# nano_relay.net
KiCad netlist of a schematic drawn in EAGLE
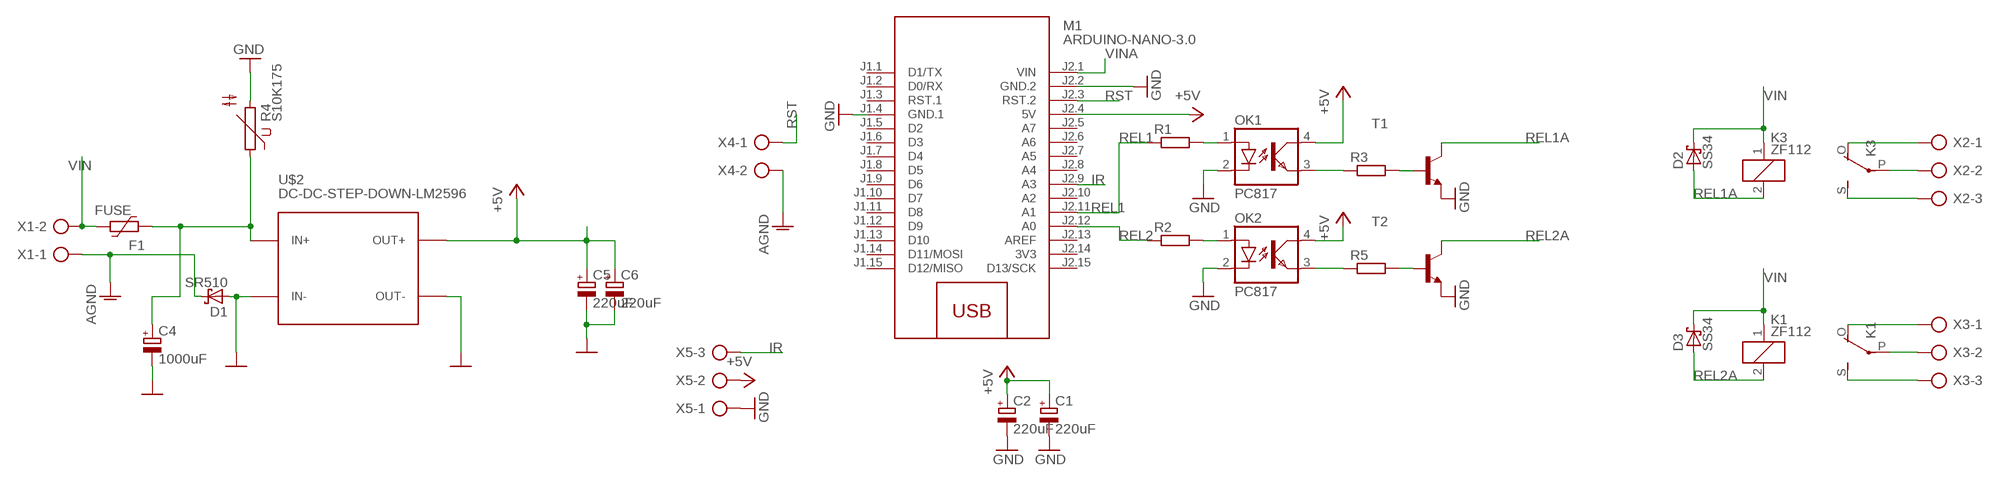
[diagram p0: schematic, sheet 1]

(export (version "E")
  (design (tool "Eeschema 10.0.6"))
  (components
    (comp (ref "C1")
      (value "220uF")
      (footprint "eagle-import:E2,5-7")
      (libsource (lib "eagle-import") (part "CPOL-EUE2.5-7"))
    )
    (comp (ref "C2")
      (value "220uF")
      (footprint "eagle-import:E2,5-7")
      (libsource (lib "eagle-import") (part "CPOL-EUE2.5-7"))
    )
    (comp (ref "C4")
      (value "1000uF")
      (footprint "eagle-import:E5-8,5")
      (libsource (lib "eagle-import") (part "CPOL-EUE5-8.5"))
    )
    (comp (ref "C5")
      (value "220uF")
      (footprint "eagle-import:E2,5-7")
      (libsource (lib "eagle-import") (part "CPOL-EUE2.5-7"))
    )
    (comp (ref "C6")
      (value "220uF")
      (footprint "eagle-import:E2,5-7")
      (libsource (lib "eagle-import") (part "CPOL-EUE2.5-7"))
    )
    (comp (ref "D1")
      (value "SR510")
      (footprint "eagle-import:SMB")
      (libsource (lib "eagle-import") (part "SCHOTTKY-DIODESMD"))
    )
    (comp (ref "D2")
      (value "SS34")
      (footprint "eagle-import:SMB")
      (libsource (lib "eagle-import") (part "SCHOTTKY-DIODESMD"))
    )
    (comp (ref "D3")
      (value "SS34")
      (footprint "eagle-import:SMB")
      (libsource (lib "eagle-import") (part "SCHOTTKY-DIODESMD"))
    )
    (comp (ref "F1")
      (value "FUSE")
      (footprint "eagle-import:1812L")
      (fields (field (name "MF") "Littelfuse") (field (name "MPN") "1812L010"))
      (libsource (lib "eagle-import") (part "?1812L010"))
    )
    (comp (ref "K1")
      (value "ZF112")
      (footprint "eagle-import:ZF112")
      (libsource (lib "eagle-import") (part "ZF112"))
    )
    (comp (ref "K3")
      (value "ZF112")
      (footprint "eagle-import:ZF112")
      (libsource (lib "eagle-import") (part "ZF112"))
    )
    (comp (ref "M1")
      (value "ARDUINO-NANO-3.0")
      (footprint "eagle-import:ARDUINO-NANO-3.0")
      (libsource (lib "eagle-import") (part "ARDUINO-NANO-3.0"))
    )
    (comp (ref "OK1")
      (value "PC817")
      (footprint "eagle-import:DIL04")
      (fields (field (name "MPN") "PC817X4J000F"))
      (libsource (lib "eagle-import") (part "PC817"))
    )
    (comp (ref "OK2")
      (value "PC817")
      (footprint "eagle-import:DIL04")
      (fields (field (name "MPN") "PC817X4J000F"))
      (libsource (lib "eagle-import") (part "PC817"))
    )
    (comp (ref "R1")
      (value "R-EU_M0805")
      (footprint "eagle-import:M0805")
      (libsource (lib "eagle-import") (part "R-EU_M0805"))
    )
    (comp (ref "R2")
      (value "R-EU_M0805")
      (footprint "eagle-import:M0805")
      (libsource (lib "eagle-import") (part "R-EU_M0805"))
    )
    (comp (ref "R3")
      (value "R-EU_M0805")
      (footprint "eagle-import:M0805")
      (libsource (lib "eagle-import") (part "R-EU_M0805"))
    )
    (comp (ref "R4")
      (value "S10K175")
      (footprint "eagle-import:S10K175")
      (libsource (lib "eagle-import") (part "S10K175"))
    )
    (comp (ref "R5")
      (value "R-EU_M0805")
      (footprint "eagle-import:M0805")
      (libsource (lib "eagle-import") (part "R-EU_M0805"))
    )
    (comp (ref "T1")
      (value "MMBT2222ALT1-NPN-SOT23-BEC")
      (footprint "eagle-import:SOT23-BEC")
      (libsource (lib "eagle-import") (part "-NPN-SOT23-BECMMBT2222ALT1"))
    )
    (comp (ref "T2")
      (value "MMBT2222ALT1-NPN-SOT23-BEC")
      (footprint "eagle-import:SOT23-BEC")
      (libsource (lib "eagle-import") (part "-NPN-SOT23-BECMMBT2222ALT1"))
    )
    (comp (ref "U$2")
      (value "DC-DC-STEP-DOWN-LM2596")
      (footprint "eagle-import:DC-DC-STEP-DOWN-LM2596")
      (libsource (lib "eagle-import") (part "DC-DC-STEP-DOWN-LM2596"))
    )
    (comp (ref "X1")
      (value "AK300/2")
      (footprint "eagle-import:AK300_2")
      (libsource (lib "eagle-import") (part "AK300/2"))
    )
    (comp (ref "X2")
      (value "AK300/3")
      (footprint "eagle-import:AK300_3")
      (libsource (lib "eagle-import") (part "AK300/3"))
    )
    (comp (ref "X3")
      (value "AK300/3")
      (footprint "eagle-import:AK300_3")
      (libsource (lib "eagle-import") (part "AK300/3"))
    )
    (comp (ref "X4")
      (value "AK300/2")
      (footprint "eagle-import:AK300_2")
      (libsource (lib "eagle-import") (part "AK300/2"))
    )
    (comp (ref "X5")
      (value "AK300/3")
      (footprint "eagle-import:AK300_3")
      (libsource (lib "eagle-import") (part "AK300/3"))
    )
  )
  (nets
    (net (code "1") (name "+5V") (class "Default")
      (node (ref "C1") (pin "+") (pinfunction "+_+") (pintype "passive"))
      (node (ref "C2") (pin "+") (pinfunction "+_+") (pintype "passive"))
      (node (ref "C5") (pin "+") (pinfunction "+_+") (pintype "passive"))
      (node (ref "C6") (pin "+") (pinfunction "+_+") (pintype "passive"))
      (node (ref "M1") (pin "J2.4") (pinfunction "5V_J2.4") (pintype "power_in"))
      (node (ref "OK1") (pin "4") (pinfunction "COL_4") (pintype "passive"))
      (node (ref "OK2") (pin "4") (pinfunction "COL_4") (pintype "passive"))
      (node (ref "U$2") (pin "OUT+") (pinfunction "OUT+_OUT+") (pintype "bidirectional"))
      (node (ref "X5") (pin "2") (pinfunction "KL_2") (pintype "passive"))
    )
    (net (code "2") (name "/3V3") (class "Default")
      (node (ref "M1") (pin "J2.14") (pinfunction "3V3_J2.14") (pintype "power_in"))
    )
    (net (code "3") (name "/IR") (class "Default")
      (node (ref "M1") (pin "J2.9") (pinfunction "A3_J2.9") (pintype "bidirectional"))
      (node (ref "X5") (pin "3") (pinfunction "KL_3") (pintype "passive"))
    )
    (net (code "4") (name "/REL1") (class "Default")
      (node (ref "M1") (pin "J2.11") (pinfunction "A1_J2.11") (pintype "bidirectional"))
      (node (ref "R1") (pin "1") (pinfunction "1_1") (pintype "passive"))
    )
    (net (code "5") (name "/REL1A") (class "Default")
      (node (ref "D2") (pin "A") (pinfunction "A_A") (pintype "passive"))
      (node (ref "K3") (pin "2") (pinfunction "2_2") (pintype "passive"))
      (node (ref "T1") (pin "C") (pinfunction "C_C") (pintype "passive"))
    )
    (net (code "6") (name "/REL2") (class "Default")
      (node (ref "M1") (pin "J2.12") (pinfunction "A0_J2.12") (pintype "bidirectional"))
      (node (ref "R2") (pin "1") (pinfunction "1_1") (pintype "passive"))
    )
    (net (code "7") (name "/REL2A") (class "Default")
      (node (ref "D3") (pin "A") (pinfunction "A_A") (pintype "passive"))
      (node (ref "K1") (pin "2") (pinfunction "2_2") (pintype "passive"))
      (node (ref "T2") (pin "C") (pinfunction "C_C") (pintype "passive"))
    )
    (net (code "8") (name "/RST") (class "Default")
      (node (ref "M1") (pin "J2.3") (pinfunction "RST.2_J2.3") (pintype "bidirectional"))
      (node (ref "X4") (pin "1") (pinfunction "KL_1") (pintype "passive"))
    )
    (net (code "9") (name "/VIN") (class "Default")
      (node (ref "D2") (pin "C") (pinfunction "C_C") (pintype "passive"))
      (node (ref "D3") (pin "C") (pinfunction "C_C") (pintype "passive"))
      (node (ref "F1") (pin "1") (pinfunction "1_1") (pintype "passive"))
      (node (ref "K1") (pin "1") (pinfunction "1_1") (pintype "passive"))
      (node (ref "K3") (pin "1") (pinfunction "1_1") (pintype "passive"))
      (node (ref "X1") (pin "2") (pinfunction "KL_2") (pintype "passive"))
    )
    (net (code "10") (name "/VINA") (class "Default")
      (node (ref "M1") (pin "J2.1") (pinfunction "VIN_J2.1") (pintype "power_in"))
    )
    (net (code "11") (name "AGND") (class "Default")
      (node (ref "D1") (pin "C") (pinfunction "C_C") (pintype "passive"))
      (node (ref "X1") (pin "1") (pinfunction "KL_1") (pintype "passive"))
      (node (ref "X4") (pin "2") (pinfunction "KL_2") (pintype "passive"))
    )
    (net (code "12") (name "GND") (class "Default")
      (node (ref "C1") (pin "-") (pinfunction "-_-") (pintype "passive"))
      (node (ref "C2") (pin "-") (pinfunction "-_-") (pintype "passive"))
      (node (ref "C4") (pin "-") (pinfunction "-_-") (pintype "passive"))
      (node (ref "C5") (pin "-") (pinfunction "-_-") (pintype "passive"))
      (node (ref "C6") (pin "-") (pinfunction "-_-") (pintype "passive"))
      (node (ref "D1") (pin "A") (pinfunction "A_A") (pintype "passive"))
      (node (ref "M1") (pin "J1.4") (pinfunction "GND.1_J1.4") (pintype "power_in"))
      (node (ref "M1") (pin "J2.2") (pinfunction "GND.2_J2.2") (pintype "power_in"))
      (node (ref "OK1") (pin "2") (pinfunction "C_2") (pintype "passive"))
      (node (ref "OK2") (pin "2") (pinfunction "C_2") (pintype "passive"))
      (node (ref "R4") (pin "2") (pinfunction "2_2") (pintype "passive"))
      (node (ref "T1") (pin "E") (pinfunction "E_E") (pintype "passive"))
      (node (ref "T2") (pin "E") (pinfunction "E_E") (pintype "passive"))
      (node (ref "U$2") (pin "IN-") (pinfunction "IN-_IN-") (pintype "bidirectional"))
      (node (ref "U$2") (pin "OUT-") (pinfunction "OUT-_OUT-") (pintype "bidirectional"))
      (node (ref "X5") (pin "1") (pinfunction "KL_1") (pintype "passive"))
    )
    (net (code "13") (name "Net-(C4-Pad+)") (class "Default")
      (node (ref "C4") (pin "+") (pinfunction "+_+") (pintype "passive"))
      (node (ref "F1") (pin "2") (pinfunction "2_2") (pintype "passive"))
      (node (ref "R4") (pin "1") (pinfunction "1_1") (pintype "passive"))
      (node (ref "U$2") (pin "IN+") (pinfunction "IN+_IN+") (pintype "bidirectional"))
    )
    (net (code "14") (name "Net-(OK1-A)") (class "Default")
      (node (ref "OK1") (pin "1") (pinfunction "A_1") (pintype "passive"))
      (node (ref "R1") (pin "2") (pinfunction "2_2") (pintype "passive"))
    )
    (net (code "15") (name "Net-(OK1-EMIT)") (class "Default")
      (node (ref "OK1") (pin "3") (pinfunction "EMIT_3") (pintype "passive"))
      (node (ref "R3") (pin "1") (pinfunction "1_1") (pintype "passive"))
    )
    (net (code "16") (name "Net-(OK2-A)") (class "Default")
      (node (ref "OK2") (pin "1") (pinfunction "A_1") (pintype "passive"))
      (node (ref "R2") (pin "2") (pinfunction "2_2") (pintype "passive"))
    )
    (net (code "17") (name "Net-(OK2-EMIT)") (class "Default")
      (node (ref "OK2") (pin "3") (pinfunction "EMIT_3") (pintype "passive"))
      (node (ref "R5") (pin "1") (pinfunction "1_1") (pintype "passive"))
    )
    (net (code "18") (name "Net-(R3-Pad2)") (class "Default")
      (node (ref "R3") (pin "2") (pinfunction "2_2") (pintype "passive"))
      (node (ref "T1") (pin "B") (pinfunction "B_B") (pintype "passive"))
    )
    (net (code "19") (name "Net-(R5-Pad2)") (class "Default")
      (node (ref "R5") (pin "2") (pinfunction "2_2") (pintype "passive"))
      (node (ref "T2") (pin "B") (pinfunction "B_B") (pintype "passive"))
    )
    (net (code "20") (name "Net-(X2A-KL)") (class "Default")
      (node (ref "K3") (pin "O") (pinfunction "O_O") (pintype "passive"))
      (node (ref "X2") (pin "1") (pinfunction "KL_1") (pintype "passive"))
    )
    (net (code "21") (name "Net-(X2B-KL)") (class "Default")
      (node (ref "K3") (pin "P") (pinfunction "P_P") (pintype "passive"))
      (node (ref "X2") (pin "2") (pinfunction "KL_2") (pintype "passive"))
    )
    (net (code "22") (name "Net-(X2C-KL)") (class "Default")
      (node (ref "K3") (pin "S") (pinfunction "S_S") (pintype "passive"))
      (node (ref "X2") (pin "3") (pinfunction "KL_3") (pintype "passive"))
    )
    (net (code "23") (name "Net-(X3A-KL)") (class "Default")
      (node (ref "K1") (pin "O") (pinfunction "O_O") (pintype "passive"))
      (node (ref "X3") (pin "1") (pinfunction "KL_1") (pintype "passive"))
    )
    (net (code "24") (name "Net-(X3B-KL)") (class "Default")
      (node (ref "K1") (pin "P") (pinfunction "P_P") (pintype "passive"))
      (node (ref "X3") (pin "2") (pinfunction "KL_2") (pintype "passive"))
    )
    (net (code "25") (name "Net-(X3C-KL)") (class "Default")
      (node (ref "K1") (pin "S") (pinfunction "S_S") (pintype "passive"))
      (node (ref "X3") (pin "3") (pinfunction "KL_3") (pintype "passive"))
    )
    (net (code "26") (name "unconnected-(M1-A2-PadJ2.10)") (class "Default")
      (node (ref "M1") (pin "J2.10") (pinfunction "A2_J2.10") (pintype "bidirectional"))
    )
    (net (code "27") (name "unconnected-(M1-A4-PadJ2.8)") (class "Default")
      (node (ref "M1") (pin "J2.8") (pinfunction "A4_J2.8") (pintype "bidirectional"))
    )
    (net (code "28") (name "unconnected-(M1-A5-PadJ2.7)") (class "Default")
      (node (ref "M1") (pin "J2.7") (pinfunction "A5_J2.7") (pintype "bidirectional"))
    )
    (net (code "29") (name "unconnected-(M1-A6-PadJ2.6)") (class "Default")
      (node (ref "M1") (pin "J2.6") (pinfunction "A6_J2.6") (pintype "bidirectional"))
    )
    (net (code "30") (name "unconnected-(M1-A7-PadJ2.5)") (class "Default")
      (node (ref "M1") (pin "J2.5") (pinfunction "A7_J2.5") (pintype "bidirectional"))
    )
    (net (code "31") (name "unconnected-(M1-AREF-PadJ2.13)") (class "Default")
      (node (ref "M1") (pin "J2.13") (pinfunction "AREF_J2.13") (pintype "bidirectional"))
    )
    (net (code "32") (name "unconnected-(M1-D0{slash}RX-PadJ1.2)") (class "Default")
      (node (ref "M1") (pin "J1.2") (pinfunction "D0/RX_J1.2") (pintype "bidirectional"))
    )
    (net (code "33") (name "unconnected-(M1-D1{slash}TX-PadJ1.1)") (class "Default")
      (node (ref "M1") (pin "J1.1") (pinfunction "D1/TX_J1.1") (pintype "bidirectional"))
    )
    (net (code "34") (name "unconnected-(M1-D2-PadJ1.5)") (class "Default")
      (node (ref "M1") (pin "J1.5") (pinfunction "D2_J1.5") (pintype "bidirectional"))
    )
    (net (code "35") (name "unconnected-(M1-D3-PadJ1.6)") (class "Default")
      (node (ref "M1") (pin "J1.6") (pinfunction "D3_J1.6") (pintype "bidirectional"))
    )
    (net (code "36") (name "unconnected-(M1-D4-PadJ1.7)") (class "Default")
      (node (ref "M1") (pin "J1.7") (pinfunction "D4_J1.7") (pintype "bidirectional"))
    )
    (net (code "37") (name "unconnected-(M1-D5-PadJ1.8)") (class "Default")
      (node (ref "M1") (pin "J1.8") (pinfunction "D5_J1.8") (pintype "bidirectional"))
    )
    (net (code "38") (name "unconnected-(M1-D6-PadJ1.9)") (class "Default")
      (node (ref "M1") (pin "J1.9") (pinfunction "D6_J1.9") (pintype "bidirectional"))
    )
    (net (code "39") (name "unconnected-(M1-D7-PadJ1.10)") (class "Default")
      (node (ref "M1") (pin "J1.10") (pinfunction "D7_J1.10") (pintype "bidirectional"))
    )
    (net (code "40") (name "unconnected-(M1-D8-PadJ1.11)") (class "Default")
      (node (ref "M1") (pin "J1.11") (pinfunction "D8_J1.11") (pintype "bidirectional"))
    )
    (net (code "41") (name "unconnected-(M1-D9-PadJ1.12)") (class "Default")
      (node (ref "M1") (pin "J1.12") (pinfunction "D9_J1.12") (pintype "bidirectional"))
    )
    (net (code "42") (name "unconnected-(M1-D10-PadJ1.13)") (class "Default")
      (node (ref "M1") (pin "J1.13") (pinfunction "D10_J1.13") (pintype "bidirectional"))
    )
    (net (code "43") (name "unconnected-(M1-D11{slash}MOSI-PadJ1.14)") (class "Default")
      (node (ref "M1") (pin "J1.14") (pinfunction "D11/MOSI_J1.14") (pintype "bidirectional"))
    )
    (net (code "44") (name "unconnected-(M1-D12{slash}MISO-PadJ1.15)") (class "Default")
      (node (ref "M1") (pin "J1.15") (pinfunction "D12/MISO_J1.15") (pintype "bidirectional"))
    )
    (net (code "45") (name "unconnected-(M1-D13{slash}SCK-PadJ2.15)") (class "Default")
      (node (ref "M1") (pin "J2.15") (pinfunction "D13/SCK_J2.15") (pintype "bidirectional"))
    )
    (net (code "46") (name "unconnected-(M1-RST.1-PadJ1.3)") (class "Default")
      (node (ref "M1") (pin "J1.3") (pinfunction "RST.1_J1.3") (pintype "bidirectional"))
    )
  )
)
